# pm.net
KiCad netlist of a schematic drawn in Altium Designer
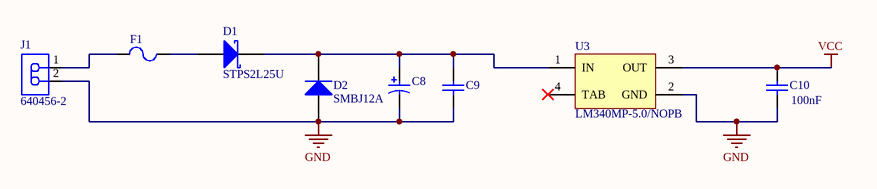
[diagram p0: pm.SchDoc]

(export (version "E")
  (design (tool "Eeschema 10.0.6"))
  (components
    (comp (ref "C8")
      (value "293D476X0025D2TE3")
      (footprint "AVX-7343-31_M")
      (description "Tantalum Capacitor, 47 uF, +/- 10%, 25 V, -55 to 125 degC, 2-Pin SMD, Tape and Reel")
      (fields (field (name "TOLERANCE") "10%") (field (name "MANUFACTURER") "AVX"))
      (libsource (lib "Altium Content Vault") (part "CMP-2000-07307-1"))
    )
    (comp (ref "C9")
      (value "330pF")
      (footprint "CAPC0805(2012)100_M")
      (description "CAP 330pF 50V ±1% 0805 (2012 Metric) Thickness 1mm SMD")
      (fields (field (name "TOLERANCE") "Â±1%"))
      (libsource (lib "Altium Content Vault") (part "CMP-1036-02496-1"))
    )
    (comp (ref "C10")
      (value "100nF")
      (footprint "CAPC0805(2012)75_M")
      (description "CAP 100nF 16V ±20% 0805 (2012 Metric) Thickness 0.75mm SMD")
      (fields (field (name "TOLERANCE") "Â±20%"))
      (libsource (lib "Altium Content Vault") (part "CMP-1036-04403-1"))
    )
    (comp (ref "D1")
      (value "STPS2L25U")
      (footprint "STM-SMB_P_V")
      (description "Low Drop Power Schottky Rectifier, 2 A, 25 V, 2-Pin SMD (SMB), RoHS, Tape and Reel")
      (fields (field (name "MANUFACTURER") "STMicroelectronics"))
      (libsource (lib "Altium Content Vault") (part "CMP-2000-07176-1"))
    )
    (comp (ref "D2")
      (value "SMBJ12A")
      (footprint "FAIR-DO-214AA-2_V")
      (fields (field (name "MANUFACTURER") "Fairchild Semiconductor"))
      (libsource (lib "Altium Content Vault") (part "CMP-2000-07093-1"))
    )
    (comp (ref "F1")
      (value "1210L050YR")
      (footprint "library pcb:fuse - duplicate")
      (libsource (lib "library") (part "FUSE"))
    )
    (comp (ref "J1")
      (value "640456-2")
      (footprint "TECO-640456-2_V")
      (fields (field (name "MANUFACTURER") "TE Connectivity"))
      (libsource (lib "Altium Content Vault") (part "CMP-2000-05417-1"))
    )
    (comp (ref "U3")
      (value "LM340MP-5.0/NOPB")
      (footprint "DCY0004A_L")
      (description "Series 3-Terminal Positive Regulators, 4-pin SOT-223, Pb-Free")
      (fields (field (name "MANUFACTURER") "Texas Instruments"))
      (libsource (lib "Altium Content Vault") (part "CMP-0062-01784-3"))
    )
  )
  (nets
    (net (code "1") (name "GND") (class "Default")
      (node (ref "C10") (pin "1") (pinfunction "1_1") (pintype "passive"))
      (node (ref "C8") (pin "2") (pinfunction "2_2") (pintype "passive"))
      (node (ref "C9") (pin "1") (pinfunction "1_1") (pintype "passive"))
      (node (ref "D2") (pin "1") (pinfunction "A_1") (pintype "passive"))
      (node (ref "J1") (pin "2") (pinfunction "2_2") (pintype "passive"))
      (node (ref "U3") (pin "2") (pinfunction "GND_2") (pintype "power_in"))
    )
    (net (code "2") (name "Net-(D1-A)") (class "Default")
      (node (ref "D1") (pin "1") (pinfunction "A_1") (pintype "passive"))
      (node (ref "F1") (pin "2") (pinfunction "2_2") (pintype "passive"))
    )
    (net (code "3") (name "Net-(D1-K)") (class "Default")
      (node (ref "C8") (pin "1") (pinfunction "1_1") (pintype "passive"))
      (node (ref "C9") (pin "2") (pinfunction "2_2") (pintype "passive"))
      (node (ref "D1") (pin "2") (pinfunction "K_2") (pintype "passive"))
      (node (ref "D2") (pin "2") (pinfunction "K_2") (pintype "passive"))
      (node (ref "U3") (pin "1") (pinfunction "IN_1") (pintype "power_in"))
    )
    (net (code "4") (name "Net-(F1-Pad1)") (class "Default")
      (node (ref "F1") (pin "1") (pinfunction "1_1") (pintype "passive"))
      (node (ref "J1") (pin "1") (pinfunction "1_1") (pintype "passive"))
    )
    (net (code "5") (name "VCC") (class "Default")
      (node (ref "C10") (pin "2") (pinfunction "2_2") (pintype "passive"))
      (node (ref "U3") (pin "3") (pinfunction "OUT_3") (pintype "power_in"))
    )
    (net (code "6") (name "unconnected-(U3-TAB-Pad4)") (class "Default")
      (node (ref "U3") (pin "4") (pinfunction "TAB_4") (pintype "power_in+no_connect"))
    )
  )
)
